# Main.net
KiCad netlist of a schematic drawn in Altium Designer
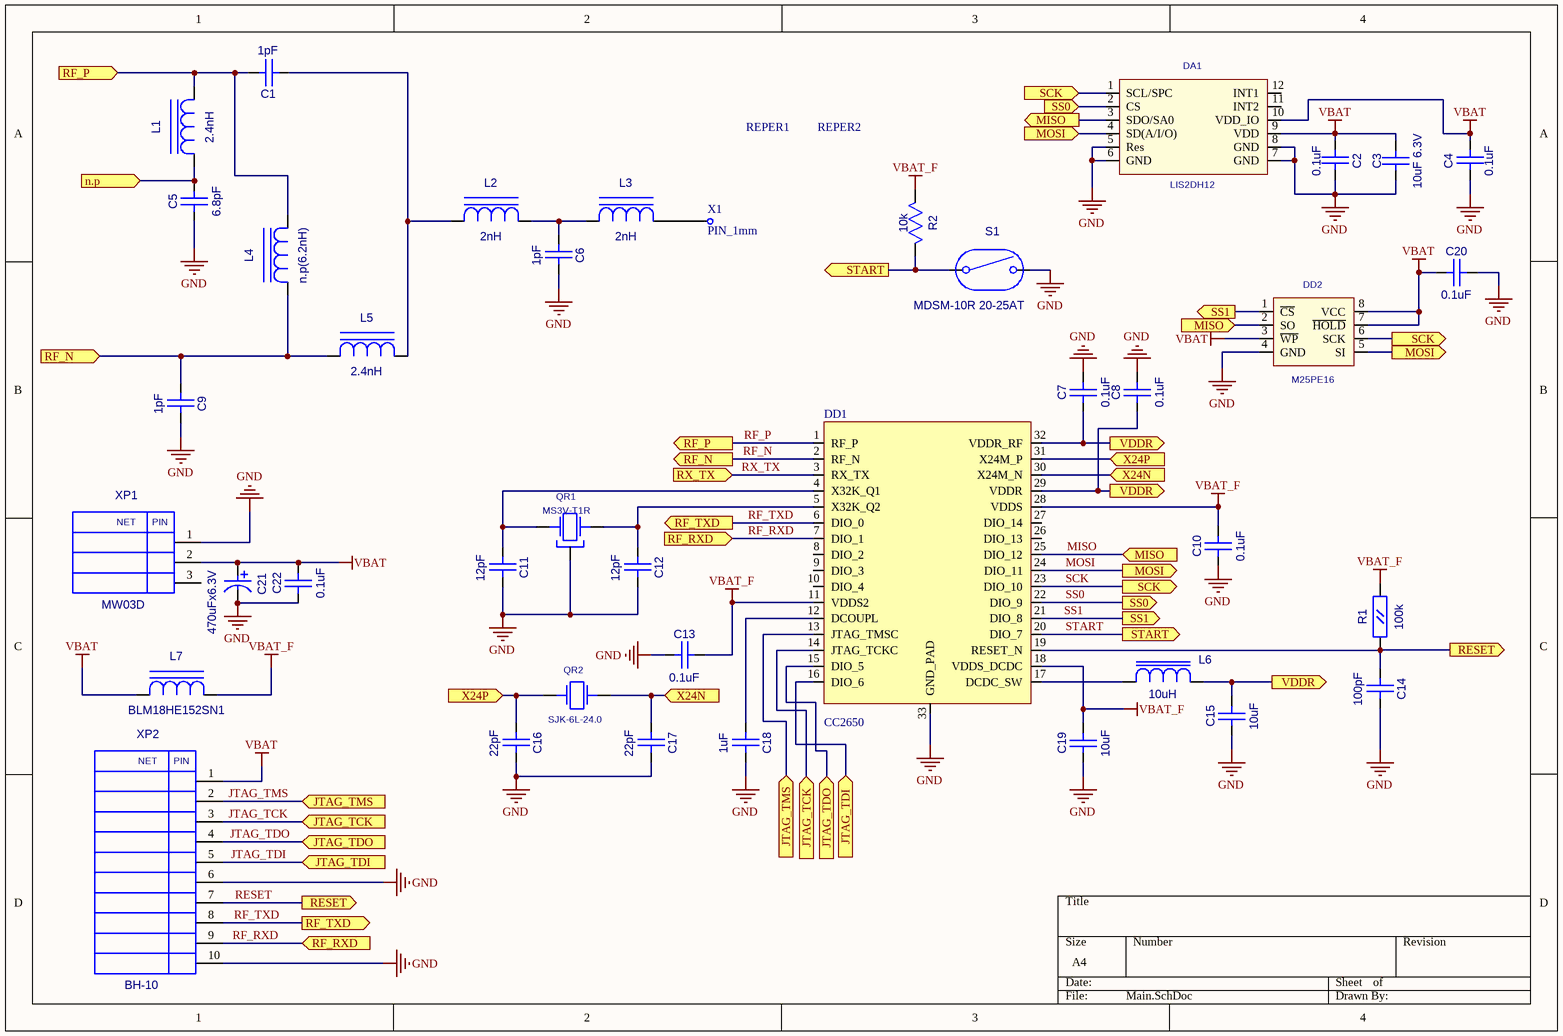
[diagram p0: Main.SchDoc]

(export (version "E")
  (design (tool "Eeschema 10.0.6"))
  (components
    (comp (ref "C1")
      (value "1pF")
      (footprint "CC0603")
      (description "CC0603")
      (libsource (lib "gprs_modem_2") (part "CC0603"))
    )
    (comp (ref "C2")
      (value "0.1uF")
      (footprint "CC0603")
      (description "CC0603")
      (libsource (lib "gprs_modem_2") (part "CC0603"))
    )
    (comp (ref "C3")
      (value "10uF 6.3V")
      (footprint "CC0805")
      (description "CC0805")
      (libsource (lib "gprs_modem_2") (part "CC0805"))
    )
    (comp (ref "C4")
      (value "0.1uF")
      (footprint "CC0603")
      (description "CC0603")
      (libsource (lib "gprs_modem_2") (part "CC0603"))
    )
    (comp (ref "C5")
      (value "6.8pF")
      (footprint "CC0603")
      (description "CC0603")
      (libsource (lib "gprs_modem_2") (part "CC0603"))
    )
    (comp (ref "C6")
      (value "1pF")
      (footprint "CC0603")
      (description "CC0603")
      (libsource (lib "gprs_modem_2") (part "CC0603"))
    )
    (comp (ref "C7")
      (value "0.1uF")
      (footprint "CC0603")
      (description "CC0603")
      (libsource (lib "gprs_modem_2") (part "CC0603"))
    )
    (comp (ref "C8")
      (value "0.1uF")
      (footprint "CC0603")
      (description "CC0603")
      (libsource (lib "gprs_modem_2") (part "CC0603"))
    )
    (comp (ref "C9")
      (value "1pF")
      (footprint "CC0603")
      (description "CC0603")
      (libsource (lib "gprs_modem_2") (part "CC0603"))
    )
    (comp (ref "C10")
      (value "0.1uF")
      (footprint "CC0603")
      (description "CC0603")
      (libsource (lib "gprs_modem_2") (part "CC0603"))
    )
    (comp (ref "C11")
      (value "12pF")
      (footprint "CC0603")
      (description "CC0603")
      (libsource (lib "gprs_modem_2") (part "CC0603"))
    )
    (comp (ref "C12")
      (value "12pF")
      (footprint "CC0603")
      (description "CC0603")
      (libsource (lib "gprs_modem_2") (part "CC0603"))
    )
    (comp (ref "C13")
      (value "0.1uF")
      (footprint "CC0603")
      (description "CC0603")
      (libsource (lib "gprs_modem_2") (part "CC0603"))
    )
    (comp (ref "C14")
      (value "100pF")
      (footprint "CC0603")
      (description "CC0603")
      (libsource (lib "gprs_modem_2") (part "CC0603"))
    )
    (comp (ref "C15")
      (value "10uF")
      (footprint "CC0805")
      (description "CC0805")
      (libsource (lib "gprs_modem_2") (part "CC0805"))
    )
    (comp (ref "C16")
      (value "22pF")
      (footprint "CC0603")
      (description "CC0603")
      (libsource (lib "gprs_modem_2") (part "CC0603"))
    )
    (comp (ref "C17")
      (value "22pF")
      (footprint "CC0603")
      (description "CC0603")
      (libsource (lib "gprs_modem_2") (part "CC0603"))
    )
    (comp (ref "C18")
      (value "1uF")
      (footprint "CC0603")
      (description "CC0603")
      (libsource (lib "gprs_modem_2") (part "CC0603"))
    )
    (comp (ref "C19")
      (value "10uF")
      (footprint "CC0805")
      (description "CC0805")
      (libsource (lib "gprs_modem_2") (part "CC0805"))
    )
    (comp (ref "C20")
      (value "0.1uF")
      (footprint "CC0603")
      (description "CC0603")
      (libsource (lib "gprs_modem_2") (part "CC0603"))
    )
    (comp (ref "C21")
      (value "470uFx6.3V")
      (footprint "TAJ-D-1M")
      (description "TAJ-D")
      (libsource (lib "gprs_modem_2") (part "TAJ-D"))
    )
    (comp (ref "C22")
      (value "0.1uF")
      (footprint "CC0603")
      (description "CC0603")
      (libsource (lib "gprs_modem_2") (part "CC0603"))
    )
    (comp (ref "DA1")
      (value "LIS2DH12")
      (footprint "LGA-12")
      (libsource (lib "gprs_modem_2") (part "LIS2DH12"))
    )
    (comp (ref "DD1")
      (value "CC2650")
      (footprint "QFN32_TI")
      (description "CC2650RHBT")
      (libsource (lib "gprs_modem_2") (part "CC2650RHB"))
    )
    (comp (ref "DD2")
      (value "M25PE16")
      (footprint "EIAJ_SO8")
      (description "S25FL016A0LMFI01")
      (libsource (lib "gprs_modem_2") (part "S25FL016A0LMFI01"))
    )
    (comp (ref "L1")
      (value "2.4nH")
      (footprint "L0603")
      (description "L0603")
      (libsource (lib "gprs_modem_2") (part "L0603"))
    )
    (comp (ref "L2")
      (value "2nH")
      (footprint "L0603")
      (description "L0603")
      (libsource (lib "gprs_modem_2") (part "L0603"))
    )
    (comp (ref "L3")
      (value "2nH")
      (footprint "L0603")
      (description "L0603")
      (libsource (lib "gprs_modem_2") (part "L0603"))
    )
    (comp (ref "L4")
      (value "n.p(6.2nH)")
      (footprint "L0603")
      (description "L0603")
      (libsource (lib "gprs_modem_2") (part "L0603"))
    )
    (comp (ref "L5")
      (value "2.4nH")
      (footprint "L0603")
      (description "L0603")
      (libsource (lib "gprs_modem_2") (part "L0603"))
    )
    (comp (ref "L6")
      (value "10uH")
      (footprint "RC0805")
      (description "L0805")
      (libsource (lib "gprs_modem_2") (part "L0805"))
    )
    (comp (ref "L7")
      (value "BLM18HE152SN1")
      (footprint "L0603")
      (description "L0603")
      (libsource (lib "gprs_modem_2") (part "L0603"))
    )
    (comp (ref "QR1")
      (value "MS3V-T1R")
      (footprint "MS3V-T1R")
      (description "CRYSTAL_32768 Hz")
      (libsource (lib "gprs_modem_2") (part "MS3V-T1R"))
    )
    (comp (ref "QR2")
      (value "SJK-6L-24.0")
      (footprint "AC5032_2")
      (description "AC5032/2")
      (libsource (lib "gprs_modem_2") (part "AC5032_2"))
    )
    (comp (ref "R1")
      (value "100k")
      (footprint "RC0603")
      (description "RC0603")
      (libsource (lib "gprs_modem_2") (part "RC0603"))
    )
    (comp (ref "R2")
      (value "10k")
      (footprint "RC0603-3M")
      (description "RC0603")
      (libsource (lib "gprs_modem") (part "RC0603"))
    )
    (comp (ref "REPER1")
      (value "REPER1.2")
      (footprint "REPER1.2")
      (libsource (lib "gprs_modem_2") (part "REPER1.2"))
    )
    (comp (ref "REPER2")
      (value "REPER1.2")
      (footprint "REPER1.2")
      (libsource (lib "gprs_modem_2") (part "REPER1.2"))
    )
    (comp (ref "S1")
      (value "MDSM-10R 20-25AT")
      (footprint "MDSM-10R")
      (description "Switch, Single Pole, Single Throw, Normally Open")
      (libsource (lib "gprs_modem") (part "MDSM-10R"))
    )
    (comp (ref "X1")
      (value "PIN_1mm")
      (footprint "PIN_1mm")
      (libsource (lib "gprs_modem_2") (part "PIN_1mm"))
    )
    (comp (ref "XP1") (value "MW03D") (footprint "MW03D") (libsource (lib "gprs_modem_2") (part "MW03D")))
    (comp (ref "XP2") (value "BH-10") (footprint "BH-10") (libsource (lib "gprs_modem_2") (part "BH-10")))
  )
  (nets
    (net (code "1") (name "/JTAG_TCK") (class "Default")
      (node (ref "DD1") (pin "14") (pinfunction "JTAG_TCKC_14") (pintype "passive"))
      (node (ref "XP2") (pin "3") (pinfunction "3_3") (pintype "passive"))
    )
    (net (code "2") (name "/JTAG_TDI") (class "Default")
      (node (ref "DD1") (pin "16") (pinfunction "DIO_6_16") (pintype "passive"))
      (node (ref "XP2") (pin "5") (pinfunction "5_5") (pintype "passive"))
    )
    (net (code "3") (name "/JTAG_TDO") (class "Default")
      (node (ref "DD1") (pin "15") (pinfunction "DIO_5_15") (pintype "passive"))
      (node (ref "XP2") (pin "4") (pinfunction "4_4") (pintype "passive"))
    )
    (net (code "4") (name "/JTAG_TMS") (class "Default")
      (node (ref "DD1") (pin "13") (pinfunction "JTAG_TMSC_13") (pintype "passive"))
      (node (ref "XP2") (pin "2") (pinfunction "2_2") (pintype "passive"))
    )
    (net (code "5") (name "/MISO") (class "Default")
      (node (ref "DA1") (pin "3") (pinfunction "SDO/SA0_3") (pintype "passive"))
      (node (ref "DD1") (pin "25") (pinfunction "DIO_12_25") (pintype "passive"))
      (node (ref "DD2") (pin "2") (pinfunction "SO_2") (pintype "passive"))
    )
    (net (code "6") (name "/MOSI") (class "Default")
      (node (ref "DA1") (pin "4") (pinfunction "SD(A/I/O)_4") (pintype "passive"))
      (node (ref "DD1") (pin "24") (pinfunction "DIO_11_24") (pintype "passive"))
      (node (ref "DD2") (pin "5") (pinfunction "SI_5") (pintype "passive"))
    )
    (net (code "7") (name "/RESET") (class "Default")
      (node (ref "C14") (pin "1") (pinfunction "A_1") (pintype "passive"))
      (node (ref "DD1") (pin "19") (pinfunction "RESET_N_19") (pintype "passive"))
      (node (ref "R1") (pin "1") (pinfunction "A_1") (pintype "passive"))
      (node (ref "XP2") (pin "7") (pinfunction "7_7") (pintype "passive"))
    )
    (net (code "8") (name "/RF_N") (class "Default")
      (node (ref "C9") (pin "1") (pinfunction "A_1") (pintype "passive"))
      (node (ref "DD1") (pin "2") (pinfunction "RF_N_2") (pintype "passive"))
      (node (ref "L4") (pin "1") (pinfunction "A_1") (pintype "passive"))
      (node (ref "L5") (pin "1") (pinfunction "A_1") (pintype "passive"))
    )
    (net (code "9") (name "/RF_P") (class "Default")
      (node (ref "C1") (pin "2") (pinfunction "B_2") (pintype "passive"))
      (node (ref "DD1") (pin "1") (pinfunction "RF_P_1") (pintype "passive"))
      (node (ref "L1") (pin "2") (pinfunction "C_2") (pintype "passive"))
      (node (ref "L4") (pin "2") (pinfunction "C_2") (pintype "passive"))
    )
    (net (code "10") (name "/RF_RXD") (class "Default")
      (node (ref "DD1") (pin "7") (pinfunction "DIO_1_7") (pintype "passive"))
      (node (ref "XP2") (pin "9") (pinfunction "9_9") (pintype "passive"))
    )
    (net (code "11") (name "/RF_TXD") (class "Default")
      (node (ref "DD1") (pin "6") (pinfunction "DIO_0_6") (pintype "passive"))
      (node (ref "XP2") (pin "8") (pinfunction "8_8") (pintype "passive"))
    )
    (net (code "12") (name "/RX_TX") (class "Default")
      (node (ref "DD1") (pin "3") (pinfunction "RX_TX_3") (pintype "passive"))
    )
    (net (code "13") (name "/SCK") (class "Default")
      (node (ref "DA1") (pin "1") (pinfunction "SCL/SPC_1") (pintype "passive"))
      (node (ref "DD1") (pin "23") (pinfunction "DIO_10_23") (pintype "passive"))
      (node (ref "DD2") (pin "6") (pinfunction "SCK_6") (pintype "passive"))
    )
    (net (code "14") (name "/SS0") (class "Default")
      (node (ref "DA1") (pin "2") (pinfunction "CS_2") (pintype "passive"))
      (node (ref "DD1") (pin "22") (pinfunction "DIO_9_22") (pintype "passive"))
    )
    (net (code "15") (name "/SS1") (class "Default")
      (node (ref "DD1") (pin "21") (pinfunction "DIO_8_21") (pintype "passive"))
      (node (ref "DD2") (pin "1") (pinfunction "~{CS}_1") (pintype "passive"))
    )
    (net (code "16") (name "/START") (class "Default")
      (node (ref "DD1") (pin "20") (pinfunction "DIO_7_20") (pintype "passive"))
      (node (ref "R2") (pin "1") (pinfunction "A_1") (pintype "passive"))
      (node (ref "S1") (pin "1") (pinfunction "1_1") (pintype "passive"))
    )
    (net (code "17") (name "/VDDR") (class "Default")
      (node (ref "C15") (pin "2") (pinfunction "B_2") (pintype "passive"))
      (node (ref "C7") (pin "1") (pinfunction "A_1") (pintype "passive"))
      (node (ref "C8") (pin "1") (pinfunction "A_1") (pintype "passive"))
      (node (ref "DD1") (pin "29") (pinfunction "VDDR_29") (pintype "passive"))
      (node (ref "DD1") (pin "32") (pinfunction "VDDR_RF_32") (pintype "passive"))
      (node (ref "L6") (pin "2") (pinfunction "B_2") (pintype "passive"))
    )
    (net (code "18") (name "/X24N") (class "Default")
      (node (ref "C17") (pin "1") (pinfunction "A_1") (pintype "passive"))
      (node (ref "DD1") (pin "30") (pinfunction "X24M_N_30") (pintype "passive"))
      (node (ref "QR2") (pin "2") (pintype "passive"))
    )
    (net (code "19") (name "/X24P") (class "Default")
      (node (ref "C16") (pin "1") (pinfunction "A_1") (pintype "passive"))
      (node (ref "DD1") (pin "31") (pinfunction "X24M_P_31") (pintype "passive"))
      (node (ref "QR2") (pin "1") (pintype "passive"))
    )
    (net (code "20") (name "/n.p") (class "Default")
      (node (ref "C5") (pin "2") (pinfunction "B_2") (pintype "passive"))
      (node (ref "L1") (pin "1") (pinfunction "A_1") (pintype "passive"))
    )
    (net (code "21") (name "GND") (class "Default")
      (node (ref "C10") (pin "1") (pinfunction "A_1") (pintype "passive"))
      (node (ref "C11") (pin "2") (pinfunction "B_2") (pintype "passive"))
      (node (ref "C12") (pin "2") (pinfunction "B_2") (pintype "passive"))
      (node (ref "C13") (pin "1") (pinfunction "A_1") (pintype "passive"))
      (node (ref "C14") (pin "2") (pinfunction "B_2") (pintype "passive"))
      (node (ref "C15") (pin "1") (pinfunction "A_1") (pintype "passive"))
      (node (ref "C16") (pin "2") (pinfunction "B_2") (pintype "passive"))
      (node (ref "C17") (pin "2") (pinfunction "B_2") (pintype "passive"))
      (node (ref "C18") (pin "2") (pinfunction "B_2") (pintype "passive"))
      (node (ref "C19") (pin "1") (pinfunction "A_1") (pintype "passive"))
      (node (ref "C2") (pin "2") (pinfunction "B_2") (pintype "passive"))
      (node (ref "C20") (pin "2") (pinfunction "B_2") (pintype "passive"))
      (node (ref "C21") (pin "2") (pinfunction "B_2") (pintype "passive"))
      (node (ref "C22") (pin "1") (pinfunction "A_1") (pintype "passive"))
      (node (ref "C3") (pin "1") (pinfunction "A_1") (pintype "passive"))
      (node (ref "C4") (pin "2") (pinfunction "B_2") (pintype "passive"))
      (node (ref "C5") (pin "1") (pinfunction "A_1") (pintype "passive"))
      (node (ref "C6") (pin "2") (pinfunction "B_2") (pintype "passive"))
      (node (ref "C7") (pin "2") (pinfunction "B_2") (pintype "passive"))
      (node (ref "C8") (pin "2") (pinfunction "B_2") (pintype "passive"))
      (node (ref "C9") (pin "2") (pinfunction "B_2") (pintype "passive"))
      (node (ref "DA1") (pin "5") (pinfunction "Res_5") (pintype "passive"))
      (node (ref "DA1") (pin "6") (pinfunction "GND_6") (pintype "passive"))
      (node (ref "DA1") (pin "7") (pinfunction "GND_7") (pintype "passive"))
      (node (ref "DA1") (pin "8") (pinfunction "GND_8") (pintype "passive"))
      (node (ref "DD1") (pin "33") (pinfunction "GND_PAD_33") (pintype "passive"))
      (node (ref "DD2") (pin "4") (pinfunction "GND_4") (pintype "passive"))
      (node (ref "QR1") (pin "3") (pinfunction "3_3") (pintype "passive"))
      (node (ref "S1") (pin "2") (pinfunction "2_2") (pintype "passive"))
      (node (ref "XP1") (pin "1") (pinfunction "1_1") (pintype "passive"))
      (node (ref "XP2") (pin "10") (pinfunction "10_10") (pintype "passive"))
      (node (ref "XP2") (pin "6") (pinfunction "6_6") (pintype "passive"))
    )
    (net (code "22") (name "Net-(C1-A)") (class "Default")
      (node (ref "C1") (pin "1") (pinfunction "A_1") (pintype "passive"))
      (node (ref "L2") (pin "1") (pinfunction "A_1") (pintype "passive"))
      (node (ref "L5") (pin "2") (pinfunction "C_2") (pintype "passive"))
    )
    (net (code "23") (name "Net-(C6-A)") (class "Default")
      (node (ref "C6") (pin "1") (pinfunction "A_1") (pintype "passive"))
      (node (ref "L2") (pin "2") (pinfunction "C_2") (pintype "passive"))
      (node (ref "L3") (pin "1") (pinfunction "A_1") (pintype "passive"))
    )
    (net (code "24") (name "Net-(C11-A)") (class "Default")
      (node (ref "C11") (pin "1") (pinfunction "A_1") (pintype "passive"))
      (node (ref "DD1") (pin "4") (pinfunction "X32K_Q1_4") (pintype "passive"))
      (node (ref "QR1") (pin "2") (pinfunction "X2_2") (pintype "passive"))
    )
    (net (code "25") (name "Net-(C12-A)") (class "Default")
      (node (ref "C12") (pin "1") (pinfunction "A_1") (pintype "passive"))
      (node (ref "DD1") (pin "5") (pinfunction "X32K_Q2_5") (pintype "passive"))
      (node (ref "QR1") (pin "1") (pinfunction "X1_1") (pintype "passive"))
    )
    (net (code "26") (name "Net-(C18-A)") (class "Default")
      (node (ref "C18") (pin "1") (pinfunction "A_1") (pintype "passive"))
      (node (ref "DD1") (pin "12") (pinfunction "DCOUPL_12") (pintype "passive"))
    )
    (net (code "27") (name "Net-(DD1-DCDC_SW)") (class "Default")
      (node (ref "DD1") (pin "17") (pinfunction "DCDC_SW_17") (pintype "passive"))
      (node (ref "L6") (pin "1") (pinfunction "A_1") (pintype "passive"))
    )
    (net (code "28") (name "Net-(L3-C)") (class "Default")
      (node (ref "L3") (pin "2") (pinfunction "C_2") (pintype "passive"))
      (node (ref "X1") (pin "1") (pinfunction "1_1") (pintype "passive"))
    )
    (net (code "29") (name "VBAT") (class "Default")
      (node (ref "C2") (pin "1") (pinfunction "A_1") (pintype "passive"))
      (node (ref "C20") (pin "1") (pinfunction "A_1") (pintype "passive"))
      (node (ref "C21") (pin "1") (pinfunction "A_1") (pintype "passive"))
      (node (ref "C22") (pin "2") (pinfunction "B_2") (pintype "passive"))
      (node (ref "C3") (pin "2") (pinfunction "B_2") (pintype "passive"))
      (node (ref "C4") (pin "1") (pinfunction "A_1") (pintype "passive"))
      (node (ref "DA1") (pin "10") (pinfunction "VDD_IO_10") (pintype "passive"))
      (node (ref "DA1") (pin "9") (pinfunction "VDD_9") (pintype "passive"))
      (node (ref "DD2") (pin "3") (pinfunction "~{WP}_3") (pintype "passive"))
      (node (ref "DD2") (pin "7") (pinfunction "~{HOLD}_7") (pintype "passive"))
      (node (ref "DD2") (pin "8") (pinfunction "VCC_8") (pintype "passive"))
      (node (ref "L7") (pin "1") (pinfunction "A_1") (pintype "passive"))
      (node (ref "XP1") (pin "2") (pinfunction "2_2") (pintype "passive"))
      (node (ref "XP2") (pin "1") (pinfunction "1_1") (pintype "passive"))
    )
    (net (code "30") (name "VBAT_F") (class "Default")
      (node (ref "C10") (pin "2") (pinfunction "B_2") (pintype "passive"))
      (node (ref "C13") (pin "2") (pinfunction "B_2") (pintype "passive"))
      (node (ref "C19") (pin "2") (pinfunction "B_2") (pintype "passive"))
      (node (ref "DD1") (pin "11") (pinfunction "VDDS2_11") (pintype "passive"))
      (node (ref "DD1") (pin "18") (pinfunction "VDDS_DCDC_18") (pintype "passive"))
      (node (ref "DD1") (pin "28") (pinfunction "VDDS_28") (pintype "passive"))
      (node (ref "L7") (pin "2") (pinfunction "C_2") (pintype "passive"))
      (node (ref "R1") (pin "2") (pinfunction "B_2") (pintype "passive"))
      (node (ref "R2") (pin "2") (pinfunction "B_2") (pintype "passive"))
    )
    (net (code "31") (name "unconnected-(DA1-INT1-Pad12)") (class "Default")
      (node (ref "DA1") (pin "12") (pinfunction "INT1_12") (pintype "passive"))
    )
    (net (code "32") (name "unconnected-(DA1-INT2-Pad11)") (class "Default")
      (node (ref "DA1") (pin "11") (pinfunction "INT2_11") (pintype "passive"))
    )
    (net (code "33") (name "unconnected-(DD1-DIO_2-Pad8)") (class "Default")
      (node (ref "DD1") (pin "8") (pinfunction "DIO_2_8") (pintype "passive"))
    )
    (net (code "34") (name "unconnected-(DD1-DIO_3-Pad9)") (class "Default")
      (node (ref "DD1") (pin "9") (pinfunction "DIO_3_9") (pintype "passive"))
    )
    (net (code "35") (name "unconnected-(DD1-DIO_4-Pad10)") (class "Default")
      (node (ref "DD1") (pin "10") (pinfunction "DIO_4_10") (pintype "passive"))
    )
    (net (code "36") (name "unconnected-(DD1-DIO_13-Pad26)") (class "Default")
      (node (ref "DD1") (pin "26") (pinfunction "DIO_13_26") (pintype "passive"))
    )
    (net (code "37") (name "unconnected-(DD1-DIO_14-Pad27)") (class "Default")
      (node (ref "DD1") (pin "27") (pinfunction "DIO_14_27") (pintype "passive"))
    )
    (net (code "38") (name "unconnected-(REPER1-Pad1)") (class "Default")
      (node (ref "REPER1") (pin "1") (pintype "passive"))
    )
    (net (code "39") (name "unconnected-(REPER2-Pad1)") (class "Default")
      (node (ref "REPER2") (pin "1") (pintype "passive"))
    )
    (net (code "40") (name "unconnected-(XP1-Pad3)") (class "Default")
      (node (ref "XP1") (pin "3") (pinfunction "3_3") (pintype "passive"))
    )
  )
)
